# Sheet1.net
KiCad netlist of a schematic drawn in Altium Designer
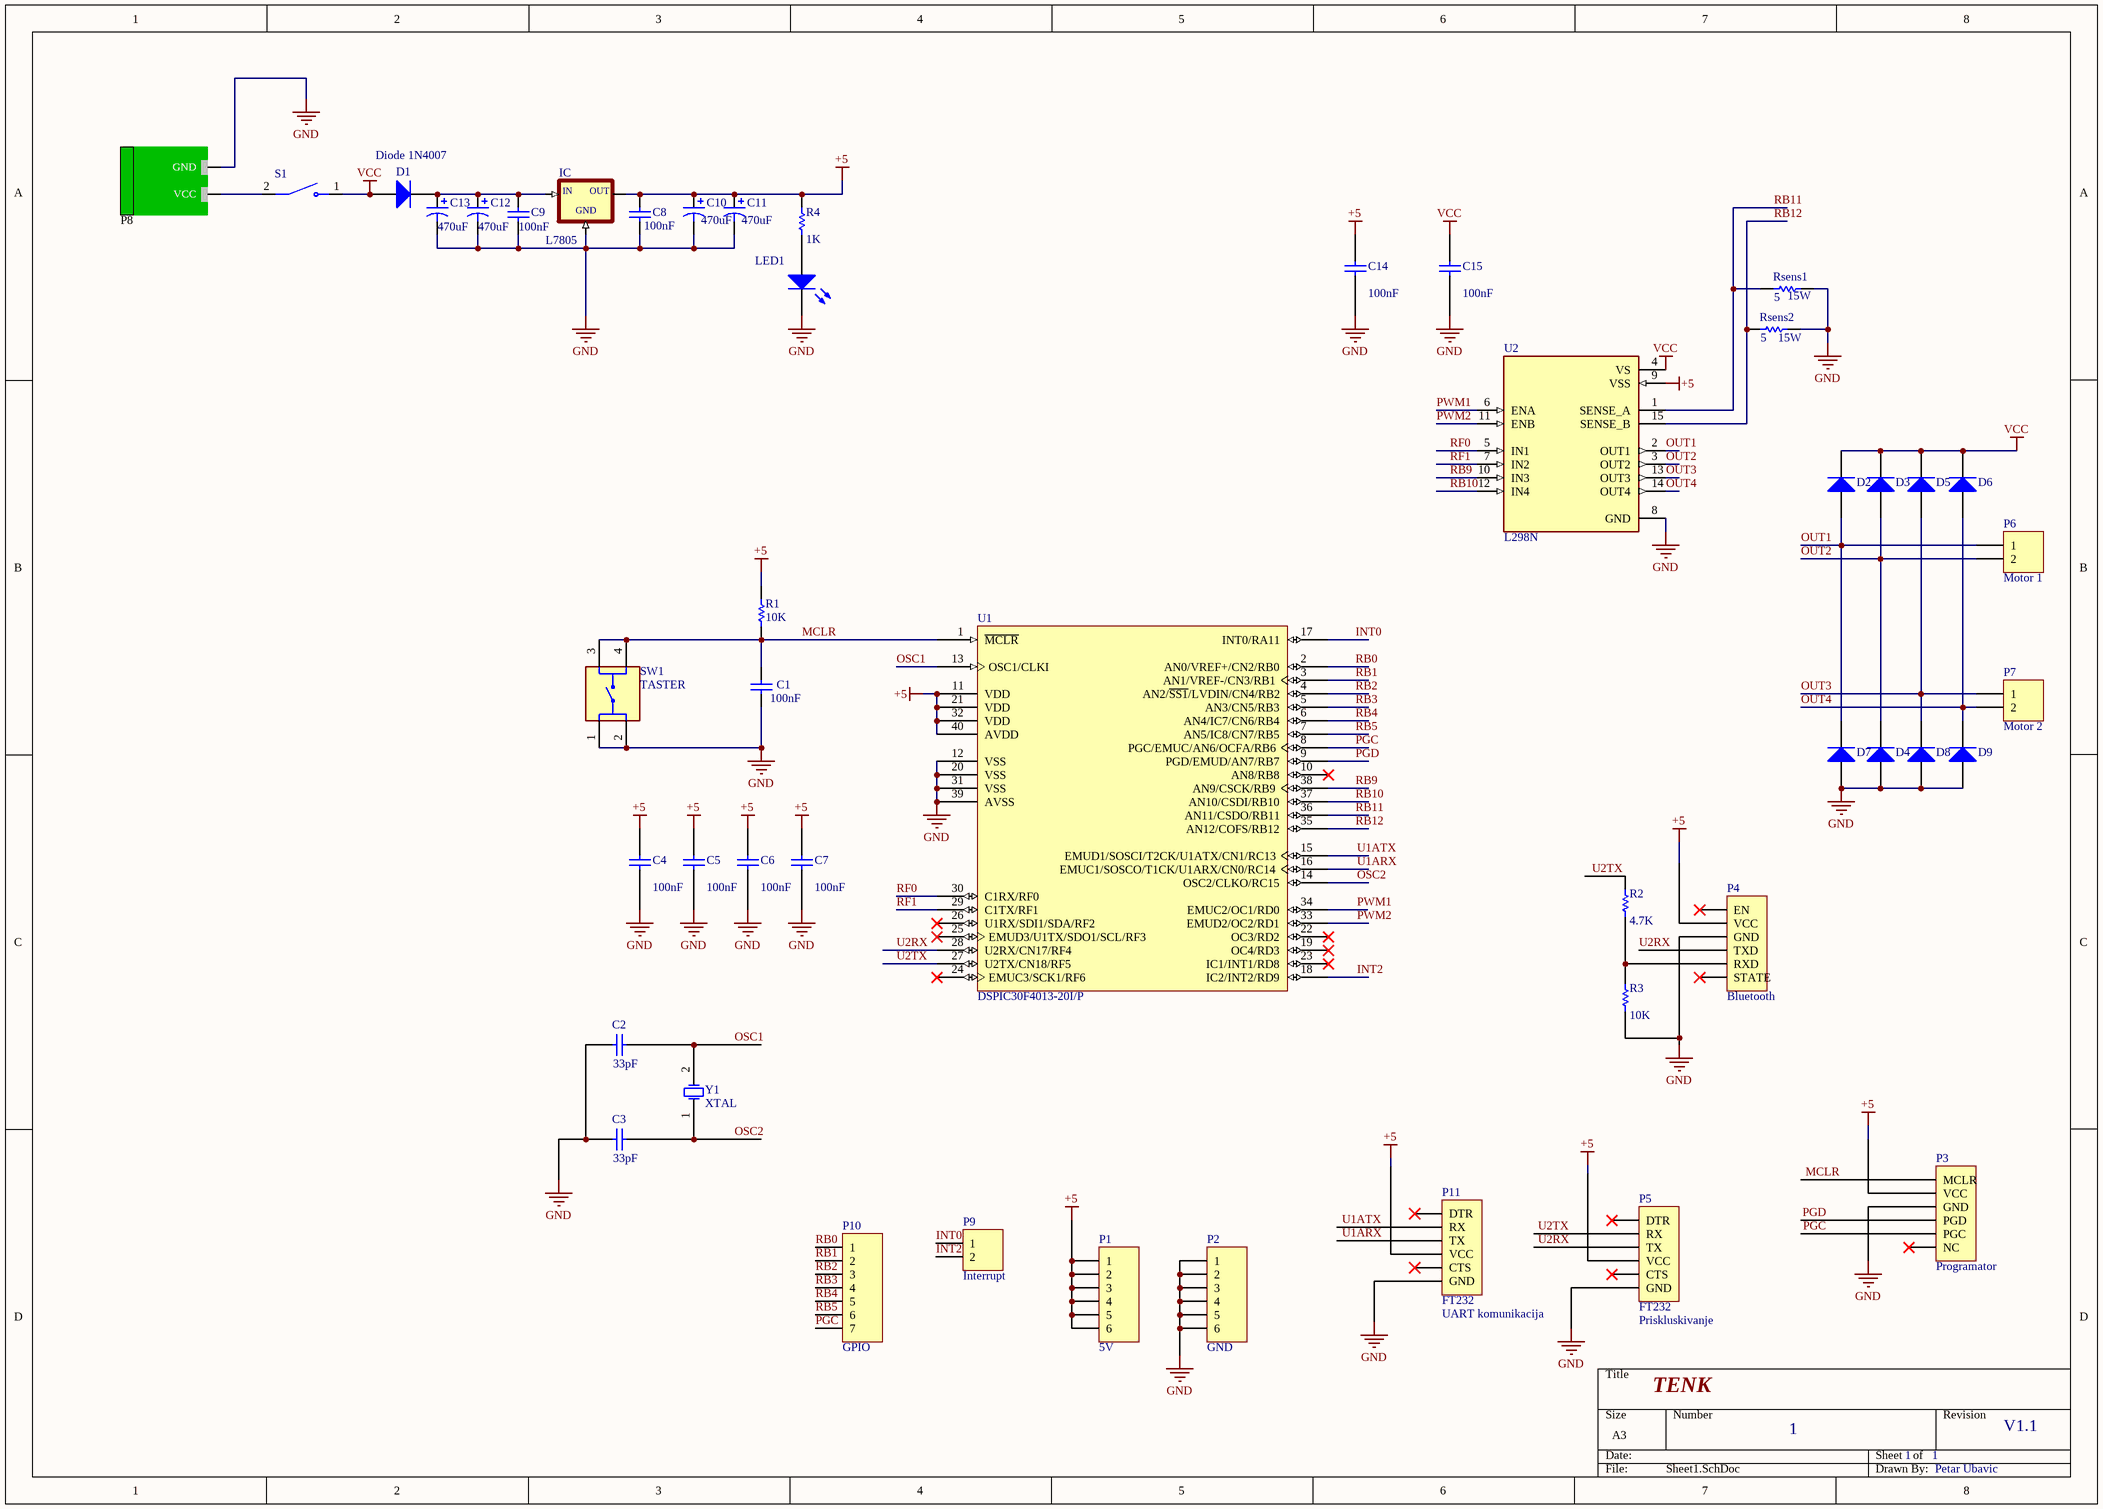
[diagram p0: Sheet1.SchDoc]

(export (version "E")
  (design (tool "Eeschema 10.0.6"))
  (components
    (comp (ref "C1")
      (value "100nF")
      (footprint "CAP200")
      (description "Capacitor")
      (fields (field (name "Comment") "Cap") (field (name "PUBLISHER") "Altium Limited"))
      (libsource (lib "Miscellaneous Devices") (part "Cap"))
    )
    (comp (ref "C2")
      (value "33pF")
      (footprint "CAP200")
      (description "Capacitor")
      (fields (field (name "Comment") "Cap") (field (name "PUBLISHER") "Altium Limited"))
      (libsource (lib "Miscellaneous Devices") (part "Cap"))
    )
    (comp (ref "C3")
      (value "33pF")
      (footprint "CAP200")
      (description "Capacitor")
      (fields (field (name "Comment") "Cap") (field (name "PUBLISHER") "Altium Limited"))
      (libsource (lib "Miscellaneous Devices") (part "Cap"))
    )
    (comp (ref "C4")
      (value "100nF")
      (footprint "CAP200")
      (description "Capacitor")
      (fields (field (name "Comment") "Cap") (field (name "PUBLISHER") "Altium Limited"))
      (libsource (lib "Miscellaneous Devices") (part "Cap"))
    )
    (comp (ref "C5")
      (value "100nF")
      (footprint "CAP200")
      (description "Capacitor")
      (fields (field (name "Comment") "Cap") (field (name "PUBLISHER") "Altium Limited"))
      (libsource (lib "Miscellaneous Devices") (part "Cap"))
    )
    (comp (ref "C6")
      (value "100nF")
      (footprint "CAP200")
      (description "Capacitor")
      (fields (field (name "Comment") "Cap") (field (name "PUBLISHER") "Altium Limited"))
      (libsource (lib "Miscellaneous Devices") (part "Cap"))
    )
    (comp (ref "C7")
      (value "100nF")
      (footprint "CAP200")
      (description "Capacitor")
      (fields (field (name "Comment") "Cap") (field (name "PUBLISHER") "Altium Limited"))
      (libsource (lib "Miscellaneous Devices") (part "Cap"))
    )
    (comp (ref "C8")
      (value "100nF")
      (footprint "CAP200")
      (description "Capacitor")
      (fields (field (name "Comment") "Cap") (field (name "PUBLISHER") "Altium Limited"))
      (libsource (lib "Miscellaneous Devices") (part "Cap"))
    )
    (comp (ref "C9")
      (value "100nF")
      (footprint "CAP200")
      (description "Capacitor")
      (fields (field (name "Comment") "Cap") (field (name "PUBLISHER") "Altium Limited"))
      (libsource (lib "Miscellaneous Devices") (part "Cap"))
    )
    (comp (ref "C10")
      (value "470uF")
      (footprint "RAD4")
      (description "Polarized Capacitor (Radial)")
      (fields (field (name "Comment") "Cap Pol1") (field (name "PUBLISHER") "Altium Limited"))
      (libsource (lib "Miscellaneous Devices") (part "Cap Pol1"))
    )
    (comp (ref "C11")
      (value "470uF")
      (footprint "RAD4")
      (description "Polarized Capacitor (Radial)")
      (fields (field (name "Comment") "Cap Pol1") (field (name "PUBLISHER") "Altium Limited"))
      (libsource (lib "Miscellaneous Devices") (part "Cap Pol1"))
    )
    (comp (ref "C12")
      (value "470uF")
      (footprint "RAD4")
      (description "Polarized Capacitor (Radial)")
      (fields (field (name "Comment") "Cap Pol1") (field (name "PUBLISHER") "Altium Limited"))
      (libsource (lib "Miscellaneous Devices") (part "Cap Pol1"))
    )
    (comp (ref "C13")
      (value "470uF")
      (footprint "RAD4")
      (description "Polarized Capacitor (Radial)")
      (fields (field (name "Comment") "Cap Pol1") (field (name "PUBLISHER") "Altium Limited"))
      (libsource (lib "Miscellaneous Devices") (part "Cap Pol1"))
    )
    (comp (ref "C14")
      (value "100nF")
      (footprint "CAP200")
      (description "Capacitor")
      (fields (field (name "Comment") "Cap") (field (name "PUBLISHER") "Altium Limited"))
      (libsource (lib "Miscellaneous Devices") (part "Cap"))
    )
    (comp (ref "C15")
      (value "100nF")
      (footprint "CAP200")
      (description "Capacitor")
      (fields (field (name "Comment") "Cap") (field (name "PUBLISHER") "Altium Limited"))
      (libsource (lib "Miscellaneous Devices") (part "Cap"))
    )
    (comp (ref "D1")
      (value "Diode 1N4007")
      (footprint "DIODE400")
      (description "1 Amp General Purpose Rectifier")
      (fields (field (name "PUBLISHER") "Altium Limited"))
      (libsource (lib "Miscellaneous Devices") (part "Diode 1N4007"))
    )
    (comp (ref "D2")
      (value "Diode 1N5402")
      (footprint "DIODE400")
      (description "3 Amp General Purpose Rectifier")
      (fields (field (name "PUBLISHER") "Altium Limited"))
      (libsource (lib "Miscellaneous Devices") (part "Diode 1N5402"))
    )
    (comp (ref "D3")
      (value "Diode 1N5402")
      (footprint "DIODE400")
      (description "3 Amp General Purpose Rectifier")
      (fields (field (name "PUBLISHER") "Altium Limited"))
      (libsource (lib "Miscellaneous Devices") (part "Diode 1N5402"))
    )
    (comp (ref "D4")
      (value "Diode 1N5402")
      (footprint "DIODE400")
      (description "3 Amp General Purpose Rectifier")
      (fields (field (name "PUBLISHER") "Altium Limited"))
      (libsource (lib "Miscellaneous Devices") (part "Diode 1N5402"))
    )
    (comp (ref "D5")
      (value "Diode 1N5402")
      (footprint "DIODE400")
      (description "3 Amp General Purpose Rectifier")
      (fields (field (name "PUBLISHER") "Altium Limited"))
      (libsource (lib "Miscellaneous Devices") (part "Diode 1N5402"))
    )
    (comp (ref "D6")
      (value "Diode 1N5402")
      (footprint "DIODE400")
      (description "3 Amp General Purpose Rectifier")
      (fields (field (name "PUBLISHER") "Altium Limited"))
      (libsource (lib "Miscellaneous Devices") (part "Diode 1N5402"))
    )
    (comp (ref "D7")
      (value "Diode 1N5402")
      (footprint "DIODE400")
      (description "3 Amp General Purpose Rectifier")
      (fields (field (name "PUBLISHER") "Altium Limited"))
      (libsource (lib "Miscellaneous Devices") (part "Diode 1N5402"))
    )
    (comp (ref "D8")
      (value "Diode 1N5402")
      (footprint "DIODE400")
      (description "3 Amp General Purpose Rectifier")
      (fields (field (name "PUBLISHER") "Altium Limited"))
      (libsource (lib "Miscellaneous Devices") (part "Diode 1N5402"))
    )
    (comp (ref "D9")
      (value "Diode 1N5402")
      (footprint "DIODE400")
      (description "3 Amp General Purpose Rectifier")
      (fields (field (name "PUBLISHER") "Altium Limited"))
      (libsource (lib "Miscellaneous Devices") (part "Diode 1N5402"))
    )
    (comp (ref "IC")
      (value "L7805")
      (footprint "78XXS")
      (description "Linear Voltage Regulator IC 1 Output 1.5A D2PAK")
      (fields (field (name "MF") "STMicroelectronics"))
      (libsource (lib "L7805") (part "L7805"))
    )
    (comp (ref "LED1")
      (value "GREEN")
      (footprint "LED_2")
      (description "Typical RED GaAs LED")
      (fields (field (name "PUBLISHER") "Altium Limited"))
      (libsource (lib "Miscellaneous Devices") (part "LED1"))
    )
    (comp (ref "P1")
      (value "5V")
      (footprint "HEADER_6")
      (description "Header, 6-Pin")
      (fields (field (name "PUBLISHER") "Altium Limited"))
      (libsource (lib "Miscellaneous Connectors") (part "Header 6"))
    )
    (comp (ref "P2")
      (value "GND")
      (footprint "HEADER_6")
      (description "Header, 6-Pin")
      (fields (field (name "PUBLISHER") "Altium Limited"))
      (libsource (lib "Miscellaneous Connectors") (part "Header 6"))
    )
    (comp (ref "P3")
      (value "Programator")
      (footprint "HEADER_6")
      (description "Header, 6-Pin")
      (fields (field (name "PUBLISHER") "Altium Limited"))
      (libsource (lib "Miscellaneous Connectors") (part "Header 6"))
    )
    (comp (ref "P4")
      (value "Bluetooth")
      (footprint "HEADER_6")
      (description "Header, 6-Pin")
      (fields (field (name "PUBLISHER") "Altium Limited"))
      (libsource (lib "Miscellaneous Connectors") (part "Header 6"))
    )
    (comp (ref "P5")
      (value "FT232")
      (footprint "HEADER_6")
      (description "Header, 6-Pin")
      (fields (field (name "PUBLISHER") "Altium Limited"))
      (libsource (lib "Miscellaneous Connectors") (part "Header 6"))
    )
    (comp (ref "P6")
      (value "Motor 1")
      (footprint "HDR1X2")
      (description "Header, 2-Pin")
      (fields (field (name "PUBLISHER") "Altium Limited"))
      (libsource (lib "Miscellaneous Connectors") (part "Header 2"))
    )
    (comp (ref "P7")
      (value "Motor 2")
      (footprint "HDR1X2")
      (description "Header, 2-Pin")
      (fields (field (name "PUBLISHER") "Altium Limited"))
      (libsource (lib "Miscellaneous Connectors") (part "Header 2"))
    )
    (comp (ref "P8")
      (value "2EDGRC-5.08-02P-14-00A(H)")
      (footprint "PWR_Con")
      (description "TERM BLOCK HDR 2POS 90DEG 5.08MM")
      (libsource (lib "Electro_Mechanical") (part "00000002"))
    )
    (comp (ref "P9")
      (value "Interrupt")
      (footprint "HDR1X2")
      (description "Header, 2-Pin")
      (fields (field (name "PUBLISHER") "Altium Limited"))
      (libsource (lib "Miscellaneous Connectors") (part "Header 2"))
    )
    (comp (ref "P10")
      (value "GPIO")
      (footprint "HDR1X7")
      (description "Header, 7-Pin")
      (fields (field (name "PUBLISHER") "Altium Limited"))
      (libsource (lib "Miscellaneous Connectors") (part "Header 7"))
    )
    (comp (ref "P11")
      (value "FT232")
      (footprint "HEADER_6")
      (description "Header, 6-Pin")
      (fields (field (name "PUBLISHER") "Altium Limited"))
      (libsource (lib "Miscellaneous Connectors") (part "Header 6"))
    )
    (comp (ref "R1")
      (value "10K")
      (footprint "RES400")
      (description "Resistor")
      (fields (field (name "Comment") "Res1") (field (name "PUBLISHER") "Altium Limited"))
      (libsource (lib "Miscellaneous Devices") (part "Res1"))
    )
    (comp (ref "R2")
      (value "4.7K")
      (footprint "RES400")
      (description "Resistor")
      (fields (field (name "Comment") "Res1") (field (name "PUBLISHER") "Altium Limited"))
      (libsource (lib "Miscellaneous Devices") (part "Res1"))
    )
    (comp (ref "R3")
      (value "10K")
      (footprint "RES400")
      (description "Resistor")
      (fields (field (name "Comment") "Res1") (field (name "PUBLISHER") "Altium Limited"))
      (libsource (lib "Miscellaneous Devices") (part "Res1"))
    )
    (comp (ref "R4")
      (value "1K")
      (footprint "RES400")
      (description "Resistor")
      (fields (field (name "Comment") "Res1") (field (name "PUBLISHER") "Altium Limited"))
      (libsource (lib "Miscellaneous Devices") (part "Res1"))
    )
    (comp (ref "Rsens1")
      (value "15W")
      (footprint "Rsens")
      (description "Resistor")
      (fields (field (name "ALTIUM_VALUE") "5") (field (name "PUBLISHER") "Altium Limited"))
      (libsource (lib "Miscellaneous Devices") (part "Res1"))
    )
    (comp (ref "Rsens2")
      (value "15W")
      (footprint "Rsens")
      (description "Resistor")
      (fields (field (name "ALTIUM_VALUE") "5") (field (name "PUBLISHER") "Altium Limited"))
      (libsource (lib "Miscellaneous Devices") (part "Res1"))
    )
    (comp (ref "S1")
      (value "~")
      (footprint "SW_RB141C1100")
      (description "Rocker Switches 15A 125VAC, OFF-ON, Black Rocker, No Markings")
      (fields (field (name "MP") "RB141C1100") (field (name "MF") "e-switch inc"))
      (libsource (lib "RB141C1100") (part "RB141C1100"))
    )
    (comp (ref "SW1")
      (value "TASTER")
      (footprint "SW_1825910-6-4")
      (description "Switch Tactile OFF (ON) SPST Round Button PC Pins 0.05A 24VDC 100000Cycles 1.57N Thru-Hole Loose")
      (fields (field (name "MP") "1825910-6"))
      (libsource (lib "1825910-6") (part "1825910-6"))
    )
    (comp (ref "U1")
      (value "DSPIC30F4013-20I/P")
      (footprint "PDIP600-P40")
      (fields (field (name "PUBLISHER") "Altium Limited"))
      (libsource (lib "Microchip DSC 16-Bit dsPIC30F") (part "DSPIC30F4013-20I/P"))
    )
    (comp (ref "U2")
      (value "L298N")
      (footprint "TO127P2020X500X2100-15")
      (description "Dual Full Bridge Motor Driver 15-Pin(15+Tab) MULTIWATT V Tube")
      (libsource (lib "L298N") (part "L298N"))
    )
    (comp (ref "Y1")
      (value "XTAL")
      (footprint "OSC_5")
      (description "Crystal Oscillator")
      (fields (field (name "PUBLISHER") "Altium Limited"))
      (libsource (lib "Miscellaneous Devices") (part "XTAL"))
    )
  )
  (nets
    (net (code "1") (name "+5") (class "Default")
      (node (ref "C10") (pin "1") (pinfunction "1_1") (pintype "passive"))
      (node (ref "C11") (pin "1") (pinfunction "1_1") (pintype "passive"))
      (node (ref "C14") (pin "2") (pinfunction "2_2") (pintype "passive"))
      (node (ref "C4") (pin "2") (pinfunction "2_2") (pintype "passive"))
      (node (ref "C5") (pin "2") (pinfunction "2_2") (pintype "passive"))
      (node (ref "C6") (pin "2") (pinfunction "2_2") (pintype "passive"))
      (node (ref "C7") (pin "2") (pinfunction "2_2") (pintype "passive"))
      (node (ref "C8") (pin "2") (pinfunction "2_2") (pintype "passive"))
      (node (ref "IC") (pin "OUT") (pinfunction "OUT_OUT") (pintype "passive"))
      (node (ref "P1") (pin "1") (pinfunction "1_1") (pintype "passive"))
      (node (ref "P1") (pin "2") (pinfunction "2_2") (pintype "passive"))
      (node (ref "P1") (pin "3") (pinfunction "3_3") (pintype "passive"))
      (node (ref "P1") (pin "4") (pinfunction "4_4") (pintype "passive"))
      (node (ref "P1") (pin "5") (pinfunction "5_5") (pintype "passive"))
      (node (ref "P1") (pin "6") (pinfunction "6_6") (pintype "passive"))
      (node (ref "P11") (pin "4") (pinfunction "4_4") (pintype "passive"))
      (node (ref "P3") (pin "2") (pinfunction "2_2") (pintype "passive"))
      (node (ref "P4") (pin "2") (pinfunction "2_2") (pintype "passive"))
      (node (ref "P5") (pin "4") (pinfunction "4_4") (pintype "passive"))
      (node (ref "R1") (pin "2") (pinfunction "2_2") (pintype "passive"))
      (node (ref "R4") (pin "2") (pinfunction "2_2") (pintype "passive"))
      (node (ref "U1") (pin "11") (pinfunction "VDD_11") (pintype "power_in"))
      (node (ref "U1") (pin "21") (pinfunction "VDD_21") (pintype "power_in"))
      (node (ref "U1") (pin "32") (pinfunction "VDD_32") (pintype "power_in"))
      (node (ref "U1") (pin "40") (pinfunction "AVDD_40") (pintype "power_in"))
      (node (ref "U2") (pin "9") (pinfunction "VSS_9") (pintype "input"))
    )
    (net (code "2") (name "/INT0") (class "Default")
      (node (ref "P9") (pin "1") (pinfunction "1_1") (pintype "passive"))
      (node (ref "U1") (pin "17") (pinfunction "INT0/RA11_17") (pintype "bidirectional"))
    )
    (net (code "3") (name "/INT2") (class "Default")
      (node (ref "P9") (pin "2") (pinfunction "2_2") (pintype "passive"))
      (node (ref "U1") (pin "18") (pinfunction "IC2/INT2/RD9_18") (pintype "bidirectional"))
    )
    (net (code "4") (name "/MCLR") (class "Default")
      (node (ref "C1") (pin "2") (pinfunction "2_2") (pintype "passive"))
      (node (ref "P3") (pin "1") (pinfunction "1_1") (pintype "passive"))
      (node (ref "R1") (pin "1") (pinfunction "1_1") (pintype "passive"))
      (node (ref "SW1") (pin "3") (pinfunction "3_3") (pintype "passive"))
      (node (ref "SW1") (pin "4") (pinfunction "4_4") (pintype "passive"))
      (node (ref "U1") (pin "1") (pinfunction "~{MCLR}_1") (pintype "input"))
    )
    (net (code "5") (name "/OSC1") (class "Default")
      (node (ref "C2") (pin "2") (pinfunction "2_2") (pintype "passive"))
      (node (ref "U1") (pin "13") (pinfunction "OSC1/CLKI_13") (pintype "input"))
      (node (ref "Y1") (pin "2") (pinfunction "OSC2_2") (pintype "passive"))
    )
    (net (code "6") (name "/OSC2") (class "Default")
      (node (ref "C3") (pin "2") (pinfunction "2_2") (pintype "passive"))
      (node (ref "U1") (pin "14") (pinfunction "OSC2/CLKO/RC15_14") (pintype "bidirectional"))
      (node (ref "Y1") (pin "1") (pinfunction "OSC1_1") (pintype "passive"))
    )
    (net (code "7") (name "/OUT1") (class "Default")
      (node (ref "D2") (pin "1") (pinfunction "A_1") (pintype "passive"))
      (node (ref "D7") (pin "2") (pinfunction "K_2") (pintype "passive"))
      (node (ref "P6") (pin "1") (pinfunction "1_1") (pintype "passive"))
      (node (ref "U2") (pin "2") (pinfunction "OUT1_2") (pintype "output"))
    )
    (net (code "8") (name "/OUT2") (class "Default")
      (node (ref "D3") (pin "1") (pinfunction "A_1") (pintype "passive"))
      (node (ref "D4") (pin "2") (pinfunction "K_2") (pintype "passive"))
      (node (ref "P6") (pin "2") (pinfunction "2_2") (pintype "passive"))
      (node (ref "U2") (pin "3") (pinfunction "OUT2_3") (pintype "output"))
    )
    (net (code "9") (name "/OUT3") (class "Default")
      (node (ref "D5") (pin "1") (pinfunction "A_1") (pintype "passive"))
      (node (ref "D8") (pin "2") (pinfunction "K_2") (pintype "passive"))
      (node (ref "P7") (pin "1") (pinfunction "1_1") (pintype "passive"))
      (node (ref "U2") (pin "13") (pinfunction "OUT3_13") (pintype "output"))
    )
    (net (code "10") (name "/OUT4") (class "Default")
      (node (ref "D6") (pin "1") (pinfunction "A_1") (pintype "passive"))
      (node (ref "D9") (pin "2") (pinfunction "K_2") (pintype "passive"))
      (node (ref "P7") (pin "2") (pinfunction "2_2") (pintype "passive"))
      (node (ref "U2") (pin "14") (pinfunction "OUT4_14") (pintype "output"))
    )
    (net (code "11") (name "/PGC") (class "Default")
      (node (ref "P10") (pin "7") (pinfunction "7_7") (pintype "passive"))
      (node (ref "P3") (pin "5") (pinfunction "5_5") (pintype "passive"))
      (node (ref "U1") (pin "8") (pinfunction "PGC/EMUC/AN6/OCFA/RB6_8") (pintype "bidirectional"))
    )
    (net (code "12") (name "/PGD") (class "Default")
      (node (ref "P3") (pin "4") (pinfunction "4_4") (pintype "passive"))
      (node (ref "U1") (pin "9") (pinfunction "PGD/EMUD/AN7/RB7_9") (pintype "bidirectional"))
    )
    (net (code "13") (name "/PWM1") (class "Default")
      (node (ref "U1") (pin "34") (pinfunction "EMUC2/OC1/RD0_34") (pintype "bidirectional"))
      (node (ref "U2") (pin "6") (pinfunction "ENA_6") (pintype "input"))
    )
    (net (code "14") (name "/PWM2") (class "Default")
      (node (ref "U1") (pin "33") (pinfunction "EMUD2/OC2/RD1_33") (pintype "bidirectional"))
      (node (ref "U2") (pin "11") (pinfunction "ENB_11") (pintype "input"))
    )
    (net (code "15") (name "/RB0") (class "Default")
      (node (ref "P10") (pin "1") (pinfunction "1_1") (pintype "passive"))
      (node (ref "U1") (pin "2") (pinfunction "AN0/VREF+/CN2/RB0_2") (pintype "bidirectional"))
    )
    (net (code "16") (name "/RB1") (class "Default")
      (node (ref "P10") (pin "2") (pinfunction "2_2") (pintype "passive"))
      (node (ref "U1") (pin "3") (pinfunction "AN1/VREF-/CN3/RB1_3") (pintype "bidirectional"))
    )
    (net (code "17") (name "/RB2") (class "Default")
      (node (ref "P10") (pin "3") (pinfunction "3_3") (pintype "passive"))
      (node (ref "U1") (pin "4") (pinfunction "AN2/~{SS1}/LVDIN/CN4/RB2_4") (pintype "bidirectional"))
    )
    (net (code "18") (name "/RB3") (class "Default")
      (node (ref "P10") (pin "4") (pinfunction "4_4") (pintype "passive"))
      (node (ref "U1") (pin "5") (pinfunction "AN3/CN5/RB3_5") (pintype "bidirectional"))
    )
    (net (code "19") (name "/RB4") (class "Default")
      (node (ref "P10") (pin "5") (pinfunction "5_5") (pintype "passive"))
      (node (ref "U1") (pin "6") (pinfunction "AN4/IC7/CN6/RB4_6") (pintype "bidirectional"))
    )
    (net (code "20") (name "/RB5") (class "Default")
      (node (ref "P10") (pin "6") (pinfunction "6_6") (pintype "passive"))
      (node (ref "U1") (pin "7") (pinfunction "AN5/IC8/CN7/RB5_7") (pintype "bidirectional"))
    )
    (net (code "21") (name "/RB9") (class "Default")
      (node (ref "U1") (pin "38") (pinfunction "AN9/CSCK/RB9_38") (pintype "bidirectional"))
      (node (ref "U2") (pin "10") (pinfunction "IN3_10") (pintype "input"))
    )
    (net (code "22") (name "/RB10") (class "Default")
      (node (ref "U1") (pin "37") (pinfunction "AN10/CSDI/RB10_37") (pintype "bidirectional"))
      (node (ref "U2") (pin "12") (pinfunction "IN4_12") (pintype "input"))
    )
    (net (code "23") (name "/RB11") (class "Default")
      (node (ref "Rsens1") (pin "1") (pinfunction "1_1") (pintype "passive"))
      (node (ref "U1") (pin "36") (pinfunction "AN11/CSDO/RB11_36") (pintype "bidirectional"))
      (node (ref "U2") (pin "1") (pinfunction "SENSE_A_1") (pintype "passive"))
    )
    (net (code "24") (name "/RB12") (class "Default")
      (node (ref "Rsens2") (pin "1") (pinfunction "1_1") (pintype "passive"))
      (node (ref "U1") (pin "35") (pinfunction "AN12/COFS/RB12_35") (pintype "bidirectional"))
      (node (ref "U2") (pin "15") (pinfunction "SENSE_B_15") (pintype "passive"))
    )
    (net (code "25") (name "/RF0") (class "Default")
      (node (ref "U1") (pin "30") (pinfunction "C1RX/RF0_30") (pintype "bidirectional"))
      (node (ref "U2") (pin "5") (pinfunction "IN1_5") (pintype "input"))
    )
    (net (code "26") (name "/RF1") (class "Default")
      (node (ref "U1") (pin "29") (pinfunction "C1TX/RF1_29") (pintype "bidirectional"))
      (node (ref "U2") (pin "7") (pinfunction "IN2_7") (pintype "input"))
    )
    (net (code "27") (name "/U1ARX") (class "Default")
      (node (ref "P11") (pin "3") (pinfunction "3_3") (pintype "passive"))
      (node (ref "U1") (pin "16") (pinfunction "EMUC1/SOSCO/T1CK/U1ARX/CN0/RC14_16") (pintype "bidirectional"))
    )
    (net (code "28") (name "/U1ATX") (class "Default")
      (node (ref "P11") (pin "2") (pinfunction "2_2") (pintype "passive"))
      (node (ref "U1") (pin "15") (pinfunction "EMUD1/SOSCI/T2CK/U1ATX/CN1/RC13_15") (pintype "bidirectional"))
    )
    (net (code "29") (name "/U2RX") (class "Default")
      (node (ref "P4") (pin "4") (pinfunction "4_4") (pintype "passive"))
      (node (ref "P5") (pin "3") (pinfunction "3_3") (pintype "passive"))
      (node (ref "U1") (pin "28") (pinfunction "U2RX/CN17/RF4_28") (pintype "bidirectional"))
    )
    (net (code "30") (name "/U2TX") (class "Default")
      (node (ref "P5") (pin "2") (pinfunction "2_2") (pintype "passive"))
      (node (ref "R2") (pin "2") (pinfunction "2_2") (pintype "passive"))
      (node (ref "U1") (pin "27") (pinfunction "U2TX/CN18/RF5_27") (pintype "bidirectional"))
    )
    (net (code "31") (name "GND") (class "Default")
      (node (ref "C1") (pin "1") (pinfunction "1_1") (pintype "passive"))
      (node (ref "C10") (pin "2") (pinfunction "2_2") (pintype "passive"))
      (node (ref "C11") (pin "2") (pinfunction "2_2") (pintype "passive"))
      (node (ref "C12") (pin "2") (pinfunction "2_2") (pintype "passive"))
      (node (ref "C13") (pin "2") (pinfunction "2_2") (pintype "passive"))
      (node (ref "C14") (pin "1") (pinfunction "1_1") (pintype "passive"))
      (node (ref "C15") (pin "1") (pinfunction "1_1") (pintype "passive"))
      (node (ref "C2") (pin "1") (pinfunction "1_1") (pintype "passive"))
      (node (ref "C3") (pin "1") (pinfunction "1_1") (pintype "passive"))
      (node (ref "C4") (pin "1") (pinfunction "1_1") (pintype "passive"))
      (node (ref "C5") (pin "1") (pinfunction "1_1") (pintype "passive"))
      (node (ref "C6") (pin "1") (pinfunction "1_1") (pintype "passive"))
      (node (ref "C7") (pin "1") (pinfunction "1_1") (pintype "passive"))
      (node (ref "C8") (pin "1") (pinfunction "1_1") (pintype "passive"))
      (node (ref "C9") (pin "1") (pinfunction "1_1") (pintype "passive"))
      (node (ref "D4") (pin "1") (pinfunction "A_1") (pintype "passive"))
      (node (ref "D7") (pin "1") (pinfunction "A_1") (pintype "passive"))
      (node (ref "D8") (pin "1") (pinfunction "A_1") (pintype "passive"))
      (node (ref "D9") (pin "1") (pinfunction "A_1") (pintype "passive"))
      (node (ref "IC") (pin "GND") (pinfunction "GND_GND") (pintype "input"))
      (node (ref "LED1") (pin "2") (pinfunction "K_2") (pintype "passive"))
      (node (ref "P11") (pin "6") (pinfunction "6_6") (pintype "passive"))
      (node (ref "P2") (pin "1") (pinfunction "1_1") (pintype "passive"))
      (node (ref "P2") (pin "2") (pinfunction "2_2") (pintype "passive"))
      (node (ref "P2") (pin "3") (pinfunction "3_3") (pintype "passive"))
      (node (ref "P2") (pin "4") (pinfunction "4_4") (pintype "passive"))
      (node (ref "P2") (pin "5") (pinfunction "5_5") (pintype "passive"))
      (node (ref "P2") (pin "6") (pinfunction "6_6") (pintype "passive"))
      (node (ref "P3") (pin "3") (pinfunction "3_3") (pintype "passive"))
      (node (ref "P4") (pin "3") (pinfunction "3_3") (pintype "passive"))
      (node (ref "P5") (pin "6") (pinfunction "6_6") (pintype "passive"))
      (node (ref "P8") (pin "1") (pinfunction "GND_1") (pintype "passive"))
      (node (ref "R3") (pin "1") (pinfunction "1_1") (pintype "passive"))
      (node (ref "Rsens1") (pin "2") (pinfunction "2_2") (pintype "passive"))
      (node (ref "Rsens2") (pin "2") (pinfunction "2_2") (pintype "passive"))
      (node (ref "SW1") (pin "1") (pinfunction "1_1") (pintype "passive"))
      (node (ref "SW1") (pin "2") (pinfunction "2_2") (pintype "passive"))
      (node (ref "U1") (pin "12") (pinfunction "VSS_12") (pintype "power_in"))
      (node (ref "U1") (pin "20") (pinfunction "VSS_20") (pintype "power_in"))
      (node (ref "U1") (pin "31") (pinfunction "VSS_31") (pintype "power_in"))
      (node (ref "U1") (pin "39") (pinfunction "AVSS_39") (pintype "power_in"))
      (node (ref "U2") (pin "8") (pinfunction "GND_8") (pintype "power_in"))
    )
    (net (code "32") (name "Net-(D1-K)") (class "Default")
      (node (ref "C12") (pin "1") (pinfunction "1_1") (pintype "passive"))
      (node (ref "C13") (pin "1") (pinfunction "1_1") (pintype "passive"))
      (node (ref "C9") (pin "2") (pinfunction "2_2") (pintype "passive"))
      (node (ref "D1") (pin "2") (pinfunction "K_2") (pintype "passive"))
      (node (ref "IC") (pin "IN") (pinfunction "IN_IN") (pintype "input"))
    )
    (net (code "33") (name "Net-(LED1-A)") (class "Default")
      (node (ref "LED1") (pin "1") (pinfunction "A_1") (pintype "passive"))
      (node (ref "R4") (pin "1") (pinfunction "1_1") (pintype "passive"))
    )
    (net (code "34") (name "Net-(P4-Pad5)") (class "Default")
      (node (ref "P4") (pin "5") (pinfunction "5_5") (pintype "passive"))
      (node (ref "R2") (pin "1") (pinfunction "1_1") (pintype "passive"))
      (node (ref "R3") (pin "2") (pinfunction "2_2") (pintype "passive"))
    )
    (net (code "35") (name "Net-(P8-VCC)") (class "Default")
      (node (ref "P8") (pin "2") (pinfunction "VCC_2") (pintype "passive"))
      (node (ref "S1") (pin "2") (pinfunction "2_2") (pintype "passive"))
    )
    (net (code "36") (name "VCC") (class "Default")
      (node (ref "C15") (pin "2") (pinfunction "2_2") (pintype "passive"))
      (node (ref "D1") (pin "1") (pinfunction "A_1") (pintype "passive"))
      (node (ref "D2") (pin "2") (pinfunction "K_2") (pintype "passive"))
      (node (ref "D3") (pin "2") (pinfunction "K_2") (pintype "passive"))
      (node (ref "D5") (pin "2") (pinfunction "K_2") (pintype "passive"))
      (node (ref "D6") (pin "2") (pinfunction "K_2") (pintype "passive"))
      (node (ref "S1") (pin "1") (pinfunction "1_1") (pintype "passive"))
      (node (ref "U2") (pin "4") (pinfunction "VS_4") (pintype "power_in"))
    )
    (net (code "37") (name "unconnected-(P3-Pad6)") (class "Default")
      (node (ref "P3") (pin "6") (pinfunction "6_6") (pintype "passive+no_connect"))
    )
    (net (code "38") (name "unconnected-(P4-Pad1)") (class "Default")
      (node (ref "P4") (pin "1") (pinfunction "1_1") (pintype "passive+no_connect"))
    )
    (net (code "39") (name "unconnected-(P4-Pad6)") (class "Default")
      (node (ref "P4") (pin "6") (pinfunction "6_6") (pintype "passive+no_connect"))
    )
    (net (code "40") (name "unconnected-(P5-Pad1)") (class "Default")
      (node (ref "P5") (pin "1") (pinfunction "1_1") (pintype "passive+no_connect"))
    )
    (net (code "41") (name "unconnected-(P5-Pad5)") (class "Default")
      (node (ref "P5") (pin "5") (pinfunction "5_5") (pintype "passive+no_connect"))
    )
    (net (code "42") (name "unconnected-(P11-Pad1)") (class "Default")
      (node (ref "P11") (pin "1") (pinfunction "1_1") (pintype "passive+no_connect"))
    )
    (net (code "43") (name "unconnected-(P11-Pad5)") (class "Default")
      (node (ref "P11") (pin "5") (pinfunction "5_5") (pintype "passive+no_connect"))
    )
    (net (code "44") (name "unconnected-(U1-AN8{slash}RB8-Pad10)") (class "Default")
      (node (ref "U1") (pin "10") (pinfunction "AN8/RB8_10") (pintype "bidirectional+no_connect"))
    )
    (net (code "45") (name "unconnected-(U1-EMUC3{slash}SCK1{slash}RF6-Pad24)") (class "Default")
      (node (ref "U1") (pin "24") (pinfunction "EMUC3/SCK1/RF6_24") (pintype "bidirectional+no_connect"))
    )
    (net (code "46") (name "unconnected-(U1-EMUD3{slash}U1TX{slash}SDO1{slash}SCL{slash}RF3-Pad25)") (class "Default")
      (node (ref "U1") (pin "25") (pinfunction "EMUD3/U1TX/SDO1/SCL/RF3_25") (pintype "bidirectional+no_connect"))
    )
    (net (code "47") (name "unconnected-(U1-IC1{slash}INT1{slash}RD8-Pad23)") (class "Default")
      (node (ref "U1") (pin "23") (pinfunction "IC1/INT1/RD8_23") (pintype "bidirectional+no_connect"))
    )
    (net (code "48") (name "unconnected-(U1-OC3{slash}RD2-Pad22)") (class "Default")
      (node (ref "U1") (pin "22") (pinfunction "OC3/RD2_22") (pintype "bidirectional+no_connect"))
    )
    (net (code "49") (name "unconnected-(U1-OC4{slash}RD3-Pad19)") (class "Default")
      (node (ref "U1") (pin "19") (pinfunction "OC4/RD3_19") (pintype "bidirectional+no_connect"))
    )
    (net (code "50") (name "unconnected-(U1-U1RX{slash}SDI1{slash}SDA{slash}RF2-Pad26)") (class "Default")
      (node (ref "U1") (pin "26") (pinfunction "U1RX/SDI1/SDA/RF2_26") (pintype "bidirectional+no_connect"))
    )
  )
)
